# design.net
KiCad netlist of a schematic drawn in Altium Designer
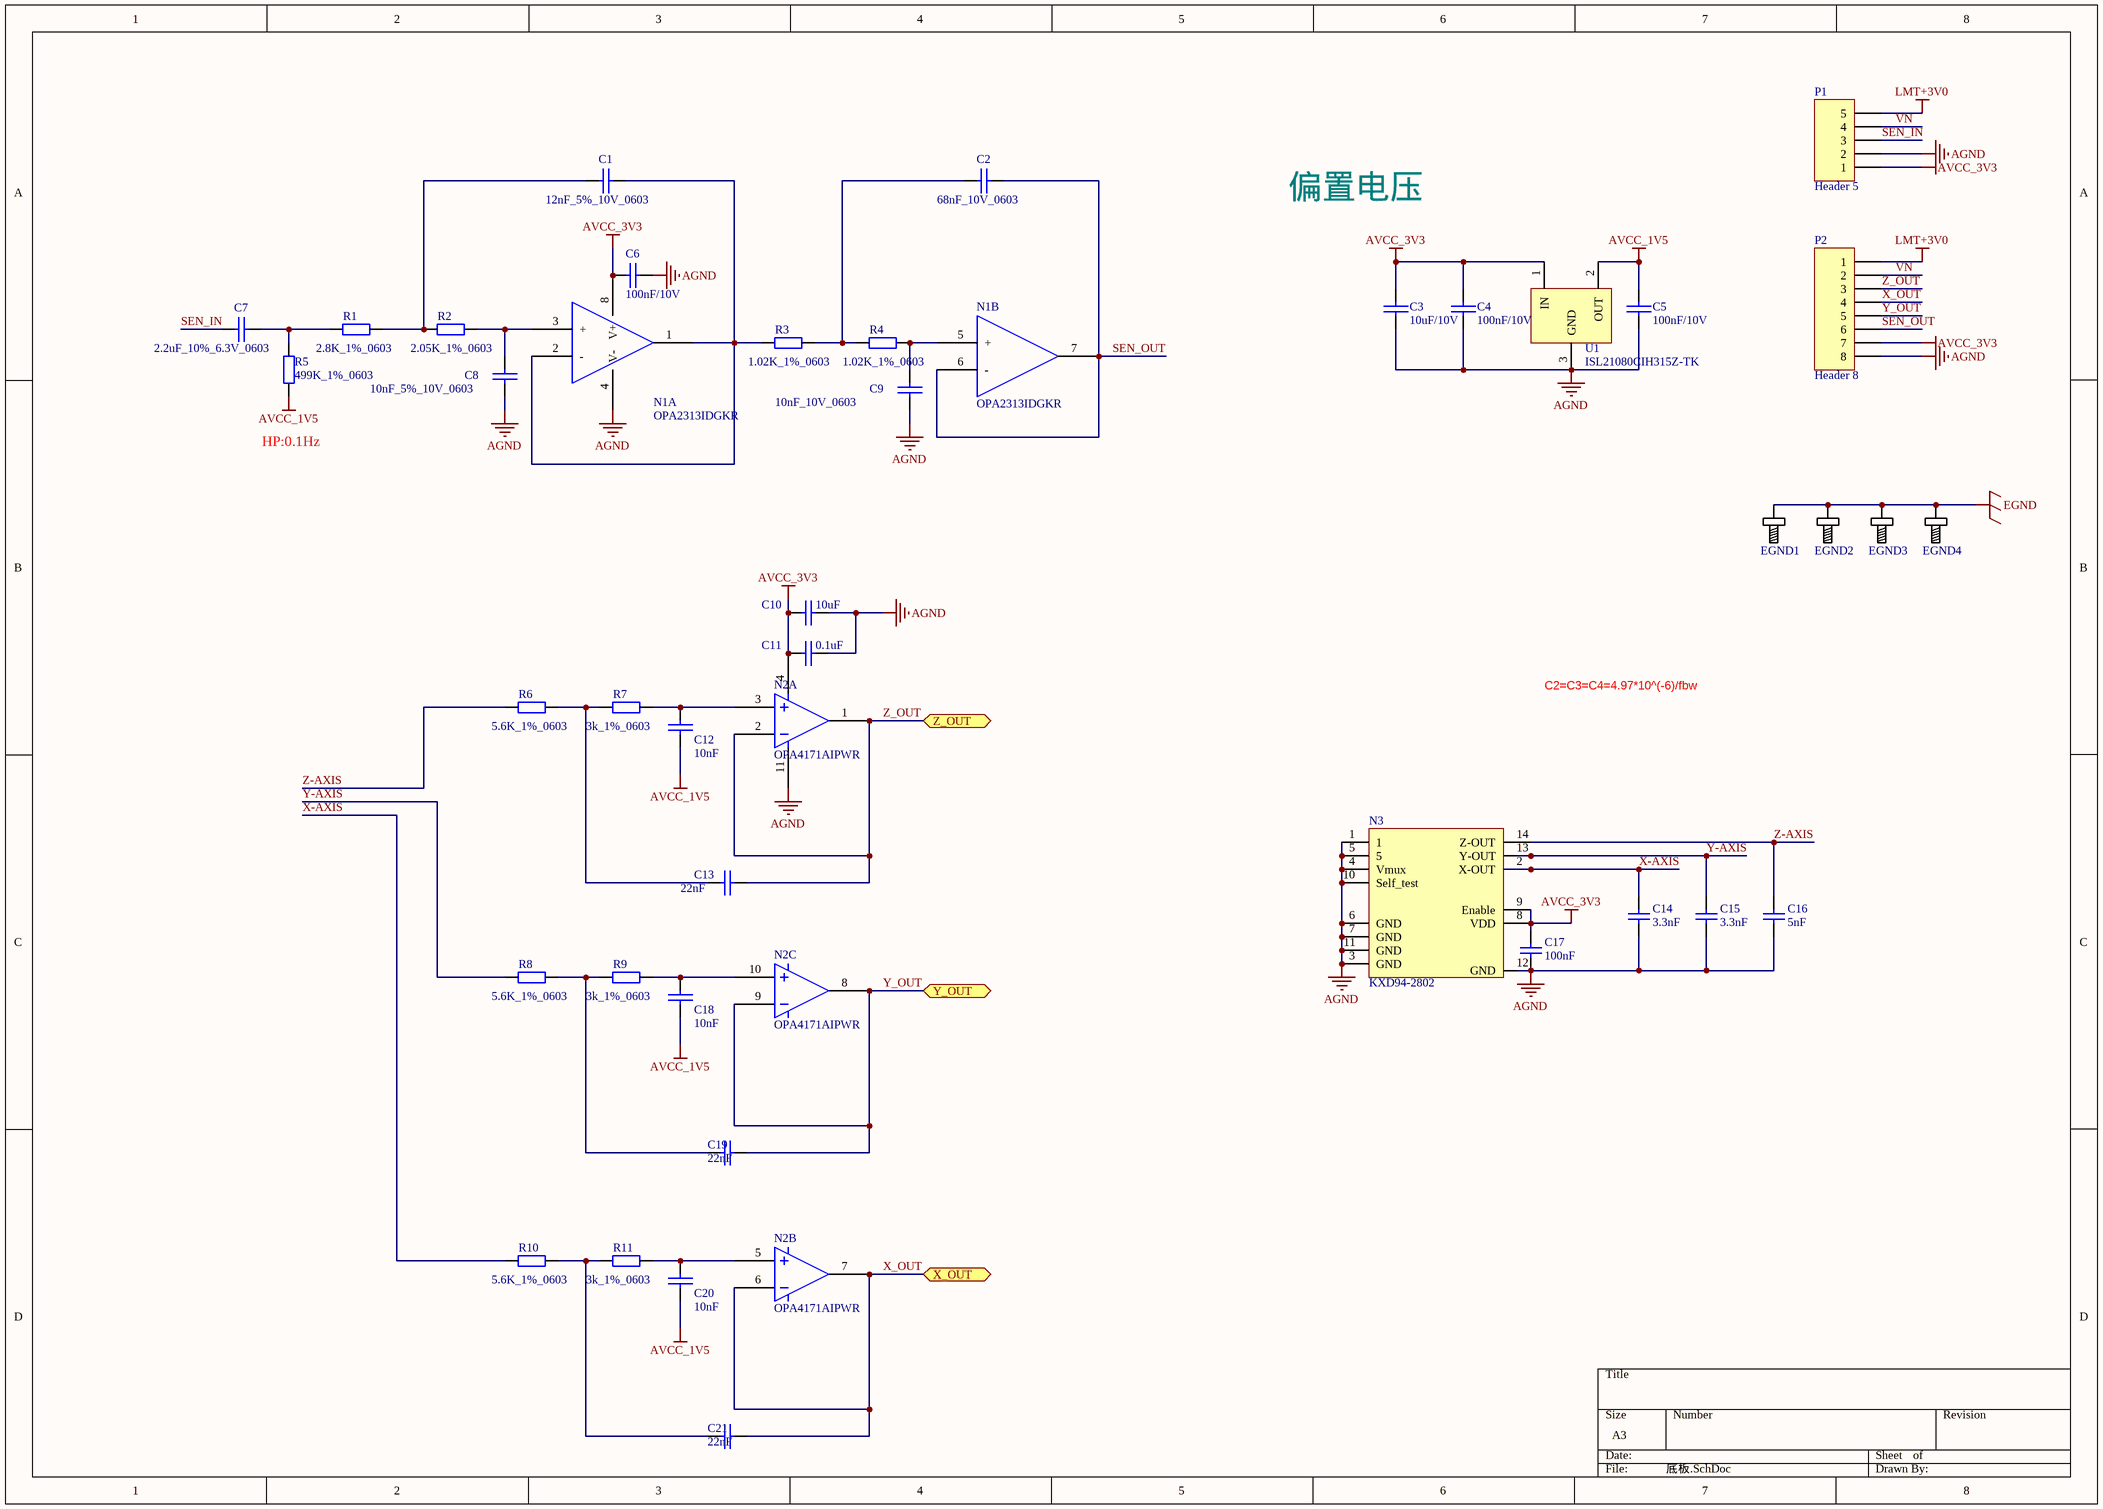
[diagram p0: 底板.SchDoc]

(export (version "E")
  (design (tool "Eeschema 10.0.6"))
  (components
    (comp (ref "C1") (value "12nF_5%_10V_0603") (footprint "0603C") (libsource (lib "*") (part "CAP")))
    (comp (ref "C2") (value "68nF_10V_0603") (footprint "0603C") (libsource (lib "*") (part "CAP")))
    (comp (ref "C3")
      (value "10uF/10V")
      (footprint "0603c")
      (description "10uF_X5R_10%_10V_0603")
      (libsource (lib "*") (part "CAP"))
    )
    (comp (ref "C4")
      (value "100nF/10V")
      (footprint "0603C")
      (description "100nF_X5R_10%_10V_0603")
      (libsource (lib "*") (part "CAP"))
    )
    (comp (ref "C5")
      (value "100nF/10V")
      (footprint "0603C")
      (description "100nF_X5R_10%_10V_0603")
      (libsource (lib "*") (part "CAP"))
    )
    (comp (ref "C6")
      (value "100nF/10V")
      (footprint "0603C")
      (description "100nF_X5R_10%_10V_0603")
      (libsource (lib "*") (part "CAP"))
    )
    (comp (ref "C7") (value "2.2uF_10%_6.3V_0603") (footprint "0603c") (libsource (lib "*") (part "CAP")))
    (comp (ref "C8") (value "10nF_5%_10V_0603") (footprint "0603C") (libsource (lib "*") (part "CAP")))
    (comp (ref "C9") (value "10nF_10V_0603") (footprint "0603C") (libsource (lib "*") (part "CAP")))
    (comp (ref "C10")
      (value "10uF")
      (footprint "0603C")
      (description "10uF_5%_10V_0603")
      (libsource (lib "") (part "CAP_1"))
    )
    (comp (ref "C11")
      (value "0.1uF")
      (footprint "0603C")
      (description "0.1uF_5%_10V_0603")
      (libsource (lib "") (part "CAP_1"))
    )
    (comp (ref "C12")
      (value "10nF")
      (footprint "0603C")
      (description "10nF_X5R_10%_10V_0603")
      (libsource (lib "") (part "CAP_2"))
    )
    (comp (ref "C13")
      (value "22nF")
      (footprint "0603C")
      (description "22nF_X5R_10%_10V_0603")
      (libsource (lib "") (part "CAP_2"))
    )
    (comp (ref "C14")
      (value "3.3nF")
      (footprint "0603C")
      (description "3.3nF_X5R_10%_10V_0603")
      (fields (field (name "PUBLISHER") "Altium Limited"))
      (libsource (lib "cjqLIB") (part "Cap"))
    )
    (comp (ref "C15")
      (value "3.3nF")
      (footprint "0603C")
      (description "3.3nF_X5R_10%_10V_0603")
      (fields (field (name "PUBLISHER") "Altium Limited"))
      (libsource (lib "cjqLIB") (part "Cap"))
    )
    (comp (ref "C16")
      (value "5nF")
      (footprint "0603C")
      (description "5nF_X5R_10%_10V_0603")
      (fields (field (name "PUBLISHER") "Altium Limited"))
      (libsource (lib "cjqLIB") (part "Cap"))
    )
    (comp (ref "C17")
      (value "100nF")
      (footprint "0603C")
      (description "Capacitor")
      (fields (field (name "PUBLISHER") "Altium Limited"))
      (libsource (lib "cjqLIB") (part "Cap"))
    )
    (comp (ref "C18")
      (value "10nF")
      (footprint "0603C")
      (description "10nF_X5R_10%_10V_0603")
      (libsource (lib "") (part "CAP_2"))
    )
    (comp (ref "C19")
      (value "22nF")
      (footprint "0603C")
      (description "22nF_X5R_10%_10V_0603")
      (libsource (lib "") (part "CAP_2"))
    )
    (comp (ref "C20")
      (value "10nF")
      (footprint "0603C")
      (description "10nF_X5R_10%_10V_0603")
      (libsource (lib "") (part "CAP_2"))
    )
    (comp (ref "C21")
      (value "22nF")
      (footprint "0603C")
      (description "22nF_X5R_10%_10V_0603")
      (libsource (lib "") (part "CAP_2"))
    )
    (comp (ref "EGND1")
      (value "EGND")
      (footprint "M2.5x4_L")
      (description "M3铜柱，长：4mm")
      (libsource (lib "Zzhsch") (part "M3x4+6_L"))
    )
    (comp (ref "EGND2")
      (value "EGND")
      (footprint "M2.5x4_L")
      (description "M3铜柱，长：4mm")
      (libsource (lib "Zzhsch") (part "M3x4+6_L"))
    )
    (comp (ref "EGND3")
      (value "EGND")
      (footprint "M2.5x4_L")
      (description "M3铜柱，长：4mm")
      (libsource (lib "Zzhsch") (part "M3x4+6_L"))
    )
    (comp (ref "EGND4")
      (value "EGND")
      (footprint "M2.5x4_L")
      (description "M3铜柱，长：4mm")
      (libsource (lib "Zzhsch") (part "M3x4+6_L"))
    )
    (comp (ref "N1")
      (value "OPA2313IDGKR")
      (footprint "MSOP8_M")
      (description "精密运放")
      (libsource (lib "Zzhsch") (part "OP262"))
    )
    (comp (ref "N2")
      (value "OPA4171AIPWR")
      (footprint "TSSOP14_L")
      (description "贴片集成电路")
      (libsource (lib "模拟集成电路") (part "LM324"))
    )
    (comp (ref "N3") (value "KXD94-2802") (footprint "LFDFN-14") (libsource (lib "Zzhsch") (part "KXR94")))
    (comp (ref "P1")
      (value "Header 5")
      (footprint "5p")
      (description "Header, 5-Pin")
      (fields (field (name "PUBLISHER") "Altium Limited"))
      (libsource (lib "Miscellaneous Connectors") (part "Header 5"))
    )
    (comp (ref "P2")
      (value "Header 8")
      (footprint "FPC1.0-2H-WS-8P")
      (description "Header, 8-Pin")
      (fields (field (name "PUBLISHER") "Altium Limited"))
      (libsource (lib "Miscellaneous Connectors") (part "Header 8"))
    )
    (comp (ref "R1")
      (value "2.8K_1%_0603")
      (footprint "0603R")
      (fields (field (name "PUBLISHER") "Altium Limited"))
      (libsource (lib "Miscellaneous Devices") (part "Res2"))
    )
    (comp (ref "R2")
      (value "2.05K_1%_0603")
      (footprint "0603R")
      (fields (field (name "PUBLISHER") "Altium Limited"))
      (libsource (lib "Miscellaneous Devices") (part "Res2"))
    )
    (comp (ref "R3")
      (value "1.02K_1%_0603")
      (footprint "0603R")
      (fields (field (name "PUBLISHER") "Altium Limited"))
      (libsource (lib "Miscellaneous Devices") (part "Res2"))
    )
    (comp (ref "R4")
      (value "1.02K_1%_0603")
      (footprint "0603R")
      (fields (field (name "PUBLISHER") "Altium Limited"))
      (libsource (lib "Miscellaneous Devices") (part "Res2"))
    )
    (comp (ref "R5")
      (value "499K_1%_0603")
      (footprint "0603R")
      (fields (field (name "PUBLISHER") "Altium Limited"))
      (libsource (lib "") (part "Res2_1"))
    )
    (comp (ref "R6")
      (value "5.6K_1%_0603")
      (footprint "0603R")
      (fields (field (name "PUBLISHER") "Altium Limited"))
      (libsource (lib "Miscellaneous Devices") (part "Res2"))
    )
    (comp (ref "R7")
      (value "3k_1%_0603")
      (footprint "0603R")
      (fields (field (name "PUBLISHER") "Altium Limited"))
      (libsource (lib "Miscellaneous Devices") (part "Res2"))
    )
    (comp (ref "R8")
      (value "5.6K_1%_0603")
      (footprint "0603R")
      (fields (field (name "PUBLISHER") "Altium Limited"))
      (libsource (lib "Miscellaneous Devices") (part "Res2"))
    )
    (comp (ref "R9")
      (value "3k_1%_0603")
      (footprint "0603R")
      (fields (field (name "PUBLISHER") "Altium Limited"))
      (libsource (lib "Miscellaneous Devices") (part "Res2"))
    )
    (comp (ref "R10")
      (value "5.6K_1%_0603")
      (footprint "0603R")
      (fields (field (name "PUBLISHER") "Altium Limited"))
      (libsource (lib "Miscellaneous Devices") (part "Res2"))
    )
    (comp (ref "R11")
      (value "3k_1%_0603")
      (footprint "0603R")
      (fields (field (name "PUBLISHER") "Altium Limited"))
      (libsource (lib "Miscellaneous Devices") (part "Res2"))
    )
    (comp (ref "U1")
      (value "ISL21080CIH315Z-TK")
      (footprint "SOT23-3N")
      (description "参考电压 1.5V")
      (libsource (lib "cjqLIB") (part "REF3025"))
    )
  )
  (nets
    (net (code "1") (name "/SEN_IN") (class "Default")
      (node (ref "C7") (pin "2") (pinfunction "2_2") (pintype "passive"))
      (node (ref "P1") (pin "3") (pinfunction "3_3") (pintype "passive"))
    )
    (net (code "2") (name "/SEN_OUT") (class "Default")
      (node (ref "C2") (pin "1") (pinfunction "1_1") (pintype "passive"))
      (node (ref "N1") (pin "6") (pinfunction "-_6") (pintype "passive"))
      (node (ref "N1") (pin "7") (pintype "passive"))
      (node (ref "P2") (pin "6") (pinfunction "6_6") (pintype "passive"))
    )
    (net (code "3") (name "/VN") (class "Default")
      (node (ref "P1") (pin "4") (pinfunction "4_4") (pintype "passive"))
      (node (ref "P2") (pin "2") (pinfunction "2_2") (pintype "passive"))
    )
    (net (code "4") (name "/X-AXIS") (class "Default")
      (node (ref "C14") (pin "1") (pinfunction "1_1") (pintype "passive"))
      (node (ref "N3") (pin "2") (pinfunction "X-OUT_2") (pintype "passive"))
      (node (ref "R10") (pin "1") (pinfunction "1_1") (pintype "passive"))
    )
    (net (code "5") (name "/X_OUT") (class "Default")
      (node (ref "C21") (pin "2") (pinfunction "2_2") (pintype "passive"))
      (node (ref "N2") (pin "6") (pintype "passive"))
      (node (ref "N2") (pin "7") (pintype "passive"))
      (node (ref "P2") (pin "4") (pinfunction "4_4") (pintype "passive"))
    )
    (net (code "6") (name "/Y-AXIS") (class "Default")
      (node (ref "C15") (pin "1") (pinfunction "1_1") (pintype "passive"))
      (node (ref "N3") (pin "13") (pinfunction "Y-OUT_13") (pintype "passive"))
      (node (ref "R8") (pin "1") (pinfunction "1_1") (pintype "passive"))
    )
    (net (code "7") (name "/Y_OUT") (class "Default")
      (node (ref "C19") (pin "2") (pinfunction "2_2") (pintype "passive"))
      (node (ref "N2") (pin "8") (pintype "passive"))
      (node (ref "N2") (pin "9") (pintype "passive"))
      (node (ref "P2") (pin "5") (pinfunction "5_5") (pintype "passive"))
    )
    (net (code "8") (name "/Z-AXIS") (class "Default")
      (node (ref "C16") (pin "1") (pinfunction "1_1") (pintype "passive"))
      (node (ref "N3") (pin "14") (pinfunction "Z-OUT_14") (pintype "passive"))
      (node (ref "R6") (pin "1") (pinfunction "1_1") (pintype "passive"))
    )
    (net (code "9") (name "/Z_OUT") (class "Default")
      (node (ref "C13") (pin "2") (pinfunction "2_2") (pintype "passive"))
      (node (ref "N2") (pin "1") (pintype "passive"))
      (node (ref "N2") (pin "2") (pintype "passive"))
      (node (ref "P2") (pin "3") (pinfunction "3_3") (pintype "passive"))
    )
    (net (code "10") (name "AGND") (class "Default")
      (node (ref "C10") (pin "1") (pinfunction "1_1") (pintype "passive"))
      (node (ref "C11") (pin "1") (pinfunction "1_1") (pintype "passive"))
      (node (ref "C14") (pin "2") (pinfunction "2_2") (pintype "passive"))
      (node (ref "C15") (pin "2") (pinfunction "2_2") (pintype "passive"))
      (node (ref "C16") (pin "2") (pinfunction "2_2") (pintype "passive"))
      (node (ref "C17") (pin "2") (pinfunction "2_2") (pintype "passive"))
      (node (ref "C3") (pin "2") (pinfunction "2_2") (pintype "passive"))
      (node (ref "C4") (pin "2") (pinfunction "2_2") (pintype "passive"))
      (node (ref "C5") (pin "2") (pinfunction "2_2") (pintype "passive"))
      (node (ref "C6") (pin "2") (pinfunction "2_2") (pintype "passive"))
      (node (ref "C8") (pin "1") (pinfunction "1_1") (pintype "passive"))
      (node (ref "C9") (pin "1") (pinfunction "1_1") (pintype "passive"))
      (node (ref "N1") (pin "4") (pinfunction "V-_4") (pintype "passive"))
      (node (ref "N2") (pin "11") (pintype "passive"))
      (node (ref "N3") (pin "1") (pinfunction "1_1") (pintype "passive"))
      (node (ref "N3") (pin "10") (pinfunction "Self_test_10") (pintype "passive"))
      (node (ref "N3") (pin "11") (pinfunction "GND_11") (pintype "passive"))
      (node (ref "N3") (pin "12") (pinfunction "GND_12") (pintype "passive"))
      (node (ref "N3") (pin "3") (pinfunction "GND_3") (pintype "passive"))
      (node (ref "N3") (pin "4") (pinfunction "Vmux_4") (pintype "passive"))
      (node (ref "N3") (pin "5") (pinfunction "5_5") (pintype "passive"))
      (node (ref "N3") (pin "6") (pinfunction "GND_6") (pintype "passive"))
      (node (ref "N3") (pin "7") (pinfunction "GND_7") (pintype "passive"))
      (node (ref "P1") (pin "2") (pinfunction "2_2") (pintype "passive"))
      (node (ref "P2") (pin "8") (pinfunction "8_8") (pintype "passive"))
      (node (ref "U1") (pin "3") (pinfunction "GND_3") (pintype "passive"))
    )
    (net (code "11") (name "AVCC_1V5") (class "Default")
      (node (ref "C12") (pin "2") (pinfunction "2_2") (pintype "passive"))
      (node (ref "C18") (pin "2") (pinfunction "2_2") (pintype "passive"))
      (node (ref "C20") (pin "2") (pinfunction "2_2") (pintype "passive"))
      (node (ref "C5") (pin "1") (pinfunction "1_1") (pintype "passive"))
      (node (ref "R5") (pin "1") (pinfunction "1_1") (pintype "passive"))
      (node (ref "U1") (pin "2") (pinfunction "OUT_2") (pintype "passive"))
    )
    (net (code "12") (name "AVCC_3V3") (class "Default")
      (node (ref "C10") (pin "2") (pinfunction "2_2") (pintype "passive"))
      (node (ref "C11") (pin "2") (pinfunction "2_2") (pintype "passive"))
      (node (ref "C17") (pin "1") (pinfunction "1_1") (pintype "passive"))
      (node (ref "C3") (pin "1") (pinfunction "1_1") (pintype "passive"))
      (node (ref "C4") (pin "1") (pinfunction "1_1") (pintype "passive"))
      (node (ref "C6") (pin "1") (pinfunction "1_1") (pintype "passive"))
      (node (ref "N1") (pin "8") (pinfunction "V+_8") (pintype "passive"))
      (node (ref "N2") (pin "4") (pintype "passive"))
      (node (ref "N3") (pin "8") (pinfunction "VDD_8") (pintype "passive"))
      (node (ref "N3") (pin "9") (pinfunction "Enable_9") (pintype "passive"))
      (node (ref "P1") (pin "1") (pinfunction "1_1") (pintype "passive"))
      (node (ref "P2") (pin "7") (pinfunction "7_7") (pintype "passive"))
      (node (ref "U1") (pin "1") (pinfunction "IN_1") (pintype "passive"))
    )
    (net (code "13") (name "EGND") (class "Default")
      (node (ref "EGND1") (pin "0") (pinfunction "0_0") (pintype "passive"))
      (node (ref "EGND2") (pin "0") (pinfunction "0_0") (pintype "passive"))
      (node (ref "EGND3") (pin "0") (pinfunction "0_0") (pintype "passive"))
      (node (ref "EGND4") (pin "0") (pinfunction "0_0") (pintype "passive"))
    )
    (net (code "14") (name "LMT+3V0") (class "Default")
      (node (ref "P1") (pin "5") (pinfunction "5_5") (pintype "passive"))
      (node (ref "P2") (pin "1") (pinfunction "1_1") (pintype "passive"))
    )
    (net (code "15") (name "Net-(C1-Pad2)") (class "Default")
      (node (ref "C1") (pin "2") (pinfunction "2_2") (pintype "passive"))
      (node (ref "R1") (pin "2") (pinfunction "2_2") (pintype "passive"))
      (node (ref "R2") (pin "1") (pinfunction "1_1") (pintype "passive"))
    )
    (net (code "16") (name "Net-(C2-Pad2)") (class "Default")
      (node (ref "C2") (pin "2") (pinfunction "2_2") (pintype "passive"))
      (node (ref "R3") (pin "2") (pinfunction "2_2") (pintype "passive"))
      (node (ref "R4") (pin "1") (pinfunction "1_1") (pintype "passive"))
    )
    (net (code "17") (name "Net-(C7-Pad1)") (class "Default")
      (node (ref "C7") (pin "1") (pinfunction "1_1") (pintype "passive"))
      (node (ref "R1") (pin "1") (pinfunction "1_1") (pintype "passive"))
      (node (ref "R5") (pin "2") (pinfunction "2_2") (pintype "passive"))
    )
    (net (code "18") (name "Net-(C12-Pad1)") (class "Default")
      (node (ref "C12") (pin "1") (pinfunction "1_1") (pintype "passive"))
      (node (ref "N2") (pin "3") (pintype "passive"))
      (node (ref "R7") (pin "2") (pinfunction "2_2") (pintype "passive"))
    )
    (net (code "19") (name "Net-(C13-Pad1)") (class "Default")
      (node (ref "C13") (pin "1") (pinfunction "1_1") (pintype "passive"))
      (node (ref "R6") (pin "2") (pinfunction "2_2") (pintype "passive"))
      (node (ref "R7") (pin "1") (pinfunction "1_1") (pintype "passive"))
    )
    (net (code "20") (name "Net-(C18-Pad1)") (class "Default")
      (node (ref "C18") (pin "1") (pinfunction "1_1") (pintype "passive"))
      (node (ref "N2") (pin "10") (pintype "passive"))
      (node (ref "R9") (pin "2") (pinfunction "2_2") (pintype "passive"))
    )
    (net (code "21") (name "Net-(C19-Pad1)") (class "Default")
      (node (ref "C19") (pin "1") (pinfunction "1_1") (pintype "passive"))
      (node (ref "R8") (pin "2") (pinfunction "2_2") (pintype "passive"))
      (node (ref "R9") (pin "1") (pinfunction "1_1") (pintype "passive"))
    )
    (net (code "22") (name "Net-(C20-Pad1)") (class "Default")
      (node (ref "C20") (pin "1") (pinfunction "1_1") (pintype "passive"))
      (node (ref "N2") (pin "5") (pintype "passive"))
      (node (ref "R11") (pin "2") (pinfunction "2_2") (pintype "passive"))
    )
    (net (code "23") (name "Net-(C21-Pad1)") (class "Default")
      (node (ref "C21") (pin "1") (pinfunction "1_1") (pintype "passive"))
      (node (ref "R10") (pin "2") (pinfunction "2_2") (pintype "passive"))
      (node (ref "R11") (pin "1") (pinfunction "1_1") (pintype "passive"))
    )
    (net (code "24") (name "Net-(N1A-+)") (class "Default")
      (node (ref "C8") (pin "2") (pinfunction "2_2") (pintype "passive"))
      (node (ref "N1") (pin "3") (pinfunction "+_3") (pintype "passive"))
      (node (ref "R2") (pin "2") (pinfunction "2_2") (pintype "passive"))
    )
    (net (code "25") (name "Net-(N1A--)") (class "Default")
      (node (ref "C1") (pin "1") (pinfunction "1_1") (pintype "passive"))
      (node (ref "N1") (pin "1") (pintype "passive"))
      (node (ref "N1") (pin "2") (pinfunction "-_2") (pintype "passive"))
      (node (ref "R3") (pin "1") (pinfunction "1_1") (pintype "passive"))
    )
    (net (code "26") (name "Net-(N1B-+)") (class "Default")
      (node (ref "C9") (pin "2") (pinfunction "2_2") (pintype "passive"))
      (node (ref "N1") (pin "5") (pinfunction "+_5") (pintype "passive"))
      (node (ref "R4") (pin "2") (pinfunction "2_2") (pintype "passive"))
    )
  )
)
